# femtoBeacon_dongle_r2_0_3.net
KiCad netlist of a schematic drawn in EAGLE
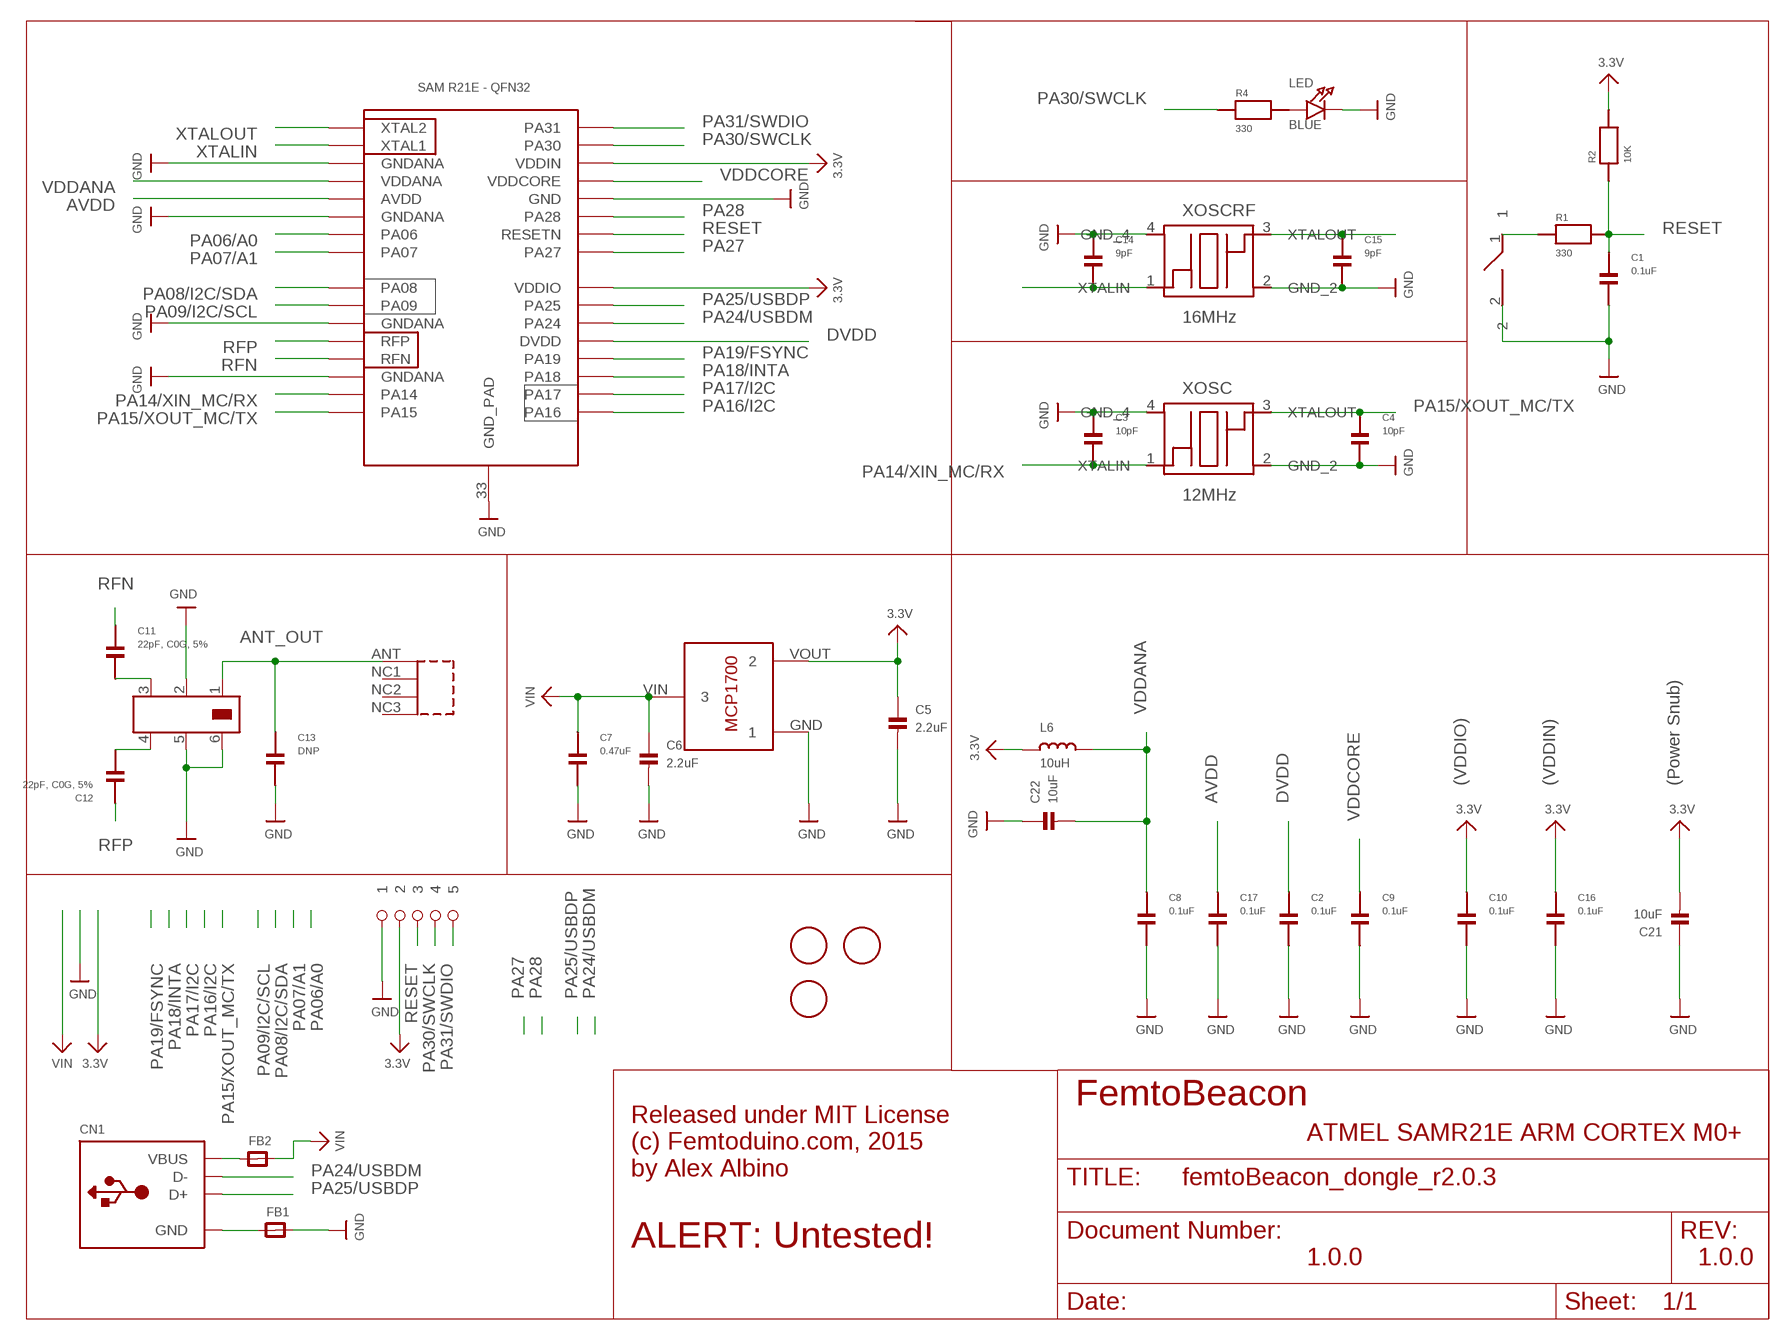
[diagram p0: schematic, sheet 1]

(export (version "E")
  (design (tool "Eeschema 10.0.6"))
  (components
    (comp (ref "BTN")
      (value "DNP")
      (footprint "eagle-import:SPST_SMD")
      (libsource (lib "eagle-import") (part "SPST_SMD"))
    )
    (comp (ref "C1")
      (value "0.1uF")
      (footprint "eagle-import:PART")
      (fields (field (name "DIGIKEY_PART") "490-3194-1-ND"))
      (libsource (lib "eagle-import") (part "CAPACITOR_0201"))
    )
    (comp (ref "C2")
      (value "0.1uF")
      (footprint "eagle-import:PART")
      (libsource (lib "eagle-import") (part "CAPACITOR_0201"))
    )
    (comp (ref "C3")
      (value "10pF")
      (footprint "eagle-import:PART")
      (fields (field (name "DIGIKEY_PART") "490-3194-1-ND"))
      (libsource (lib "eagle-import") (part "CAPACITOR_0201"))
    )
    (comp (ref "C4")
      (value "10pF")
      (footprint "eagle-import:PART")
      (fields (field (name "DIGIKEY_PART") "490-3194-1-ND"))
      (libsource (lib "eagle-import") (part "CAPACITOR_0201"))
    )
    (comp (ref "C5")
      (value "2.2uF")
      (footprint "eagle-import:_0402MP")
      (libsource (lib "eagle-import") (part "CAP_CERAMIC_0402MP"))
    )
    (comp (ref "C6")
      (value "2.2uF")
      (footprint "eagle-import:_0402MP")
      (libsource (lib "eagle-import") (part "CAP_CERAMIC_0402MP"))
    )
    (comp (ref "C7")
      (value "0.47uF")
      (footprint "eagle-import:PART")
      (libsource (lib "eagle-import") (part "CAPACITOR_0201"))
    )
    (comp (ref "C8")
      (value "0.1uF")
      (footprint "eagle-import:PART")
      (fields (field (name "DIGIKEY_PART") "490-3194-1-ND"))
      (libsource (lib "eagle-import") (part "CAPACITOR_0201"))
    )
    (comp (ref "C9")
      (value "0.1uF")
      (footprint "eagle-import:PART")
      (fields (field (name "DIGIKEY_PART") "490-3194-1-ND"))
      (libsource (lib "eagle-import") (part "CAPACITOR_0201"))
    )
    (comp (ref "C10")
      (value "0.1uF")
      (footprint "eagle-import:PART")
      (fields (field (name "DIGIKEY_PART") "490-3194-1-ND"))
      (libsource (lib "eagle-import") (part "CAPACITOR_0201"))
    )
    (comp (ref "C11")
      (value "22pF, C0G, 5%")
      (footprint "eagle-import:PART")
      (fields (field (name "DIGIKEY_PART") "490-3194-1-ND"))
      (libsource (lib "eagle-import") (part "CAPACITOR_0201"))
    )
    (comp (ref "C12")
      (value "22pF, C0G, 5%")
      (footprint "eagle-import:PART")
      (fields (field (name "DIGIKEY_PART") "490-3194-1-ND"))
      (libsource (lib "eagle-import") (part "CAPACITOR_0201"))
    )
    (comp (ref "C13")
      (value "DNP")
      (footprint "eagle-import:PART")
      (fields (field (name "DIGIKEY_PART") "490-3194-1-ND"))
      (libsource (lib "eagle-import") (part "CAPACITOR_0201"))
    )
    (comp (ref "C14")
      (value "9pF")
      (footprint "eagle-import:PART")
      (fields (field (name "DIGIKEY_PART") "490-3194-1-ND"))
      (libsource (lib "eagle-import") (part "CAPACITOR_0201"))
    )
    (comp (ref "C15")
      (value "9pF")
      (footprint "eagle-import:PART")
      (fields (field (name "DIGIKEY_PART") "490-3194-1-ND"))
      (libsource (lib "eagle-import") (part "CAPACITOR_0201"))
    )
    (comp (ref "C16")
      (value "0.1uF")
      (footprint "eagle-import:PART")
      (fields (field (name "DIGIKEY_PART") "490-3194-1-ND"))
      (libsource (lib "eagle-import") (part "CAPACITOR_0201"))
    )
    (comp (ref "C17")
      (value "0.1uF")
      (footprint "eagle-import:PART")
      (fields (field (name "DIGIKEY_PART") "490-3194-1-ND"))
      (libsource (lib "eagle-import") (part "CAPACITOR_0201"))
    )
    (comp (ref "C21")
      (value "10uF")
      (footprint "eagle-import:_0402MP")
      (libsource (lib "eagle-import") (part "CAP_CERAMIC_0402MP"))
    )
    (comp (ref "C22")
      (value "10uF")
      (footprint "eagle-import:_0402MP")
      (libsource (lib "eagle-import") (part "CAP_CERAMIC_0402MP"))
    )
    (comp (ref "CN1")
      (value "USB_TYPEA")
      (footprint "eagle-import:USB_A-SMT")
      (libsource (lib "eagle-import") (part "USB_TYPEA"))
    )
    (comp (ref "FB1")
      (value "FERRITE_0603MP")
      (footprint "eagle-import:_0603MP")
      (libsource (lib "eagle-import") (part "FERRITE_0603MP"))
    )
    (comp (ref "FB2")
      (value "FERRITE_0603MP")
      (footprint "eagle-import:_0603MP")
      (libsource (lib "eagle-import") (part "FERRITE_0603MP"))
    )
    (comp (ref "FID1")
      (value "FIDUCIAL")
      (footprint "eagle-import:FIDUCIAL_1MM")
      (libsource (lib "eagle-import") (part "FIDUCIAL"))
    )
    (comp (ref "FID2")
      (value "FIDUCIAL")
      (footprint "eagle-import:FIDUCIAL_1MM")
      (libsource (lib "eagle-import") (part "FIDUCIAL"))
    )
    (comp (ref "FID3")
      (value "FIDUCIAL")
      (footprint "eagle-import:FIDUCIAL_1MM")
      (libsource (lib "eagle-import") (part "FIDUCIAL"))
    )
    (comp (ref "L6")
      (value "10uH")
      (footprint "eagle-import:_0603MP")
      (libsource (lib "eagle-import") (part "INDUCTOR_0603MP"))
    )
    (comp (ref "LDO_VREG")
      (value "MCP1700T-3302E/TT")
      (footprint "eagle-import:MCP1700T-3302E_TT")
      (libsource (lib "eagle-import") (part "MCP1700T-3302E/TT"))
    )
    (comp (ref "LED")
      (value "BLUE")
      (footprint "eagle-import:CHIPLED_0603_NOOUTLINE")
      (libsource (lib "eagle-import") (part "LED0603_NOOUTLINE"))
    )
    (comp (ref "R1")
      (value "330")
      (footprint "eagle-import:PART")
      (libsource (lib "eagle-import") (part "RESISTOR_0201"))
    )
    (comp (ref "R2")
      (value "10K")
      (footprint "eagle-import:PART")
      (libsource (lib "eagle-import") (part "RESISTOR_0201"))
    )
    (comp (ref "R4")
      (value "330")
      (footprint "eagle-import:PART")
      (libsource (lib "eagle-import") (part "RESISTOR_0201"))
    )
    (comp (ref "U$1")
      (value "1X5_ROUND")
      (footprint "eagle-import:1X5_ROUND")
      (libsource (lib "eagle-import") (part "1X5_ROUND"))
    )
    (comp (ref "U$6")
      (value "0479480001")
      (footprint "eagle-import:0479480001")
      (libsource (lib "eagle-import") (part "0479480001"))
    )
    (comp (ref "U$12")
      (value "JOHANSON_2450BM15A0015E")
      (footprint "eagle-import:0805_BALUN")
      (libsource (lib "eagle-import") (part "JOHANSON_2450BM15A0015E"))
    )
    (comp (ref "U$76")
      (value "ATSAMR21E18A-MUT")
      (footprint "eagle-import:QFN32")
      (libsource (lib "eagle-import") (part "ATSAMR21E18A-MUT"))
    )
    (comp (ref "XOSC")
      (value "12MHz")
      (footprint "eagle-import:TSX-3225")
      (libsource (lib "eagle-import") (part "TSX-3225"))
    )
    (comp (ref "XOSCRF")
      (value "16MHz")
      (footprint "eagle-import:TSX-3225")
      (libsource (lib "eagle-import") (part "TSX-3225"))
    )
  )
  (nets
    (net (code "1") (name "/ANT_OUT") (class "Default")
      (node (ref "C13") (pin "1") (pinfunction "P$1_1") (pintype "bidirectional"))
      (node (ref "U$12") (pin "1") (pinfunction "1_1") (pintype "bidirectional"))
      (node (ref "U$6") (pin "ANT") (pinfunction "1_ANT") (pintype "bidirectional"))
    )
    (net (code "2") (name "/AVDD") (class "Default")
      (node (ref "C17") (pin "1") (pinfunction "P$1_1") (pintype "bidirectional"))
      (node (ref "U$76") (pin "5") (pinfunction "AVDD_5") (pintype "bidirectional"))
    )
    (net (code "3") (name "/DVDD") (class "Default")
      (node (ref "C2") (pin "1") (pinfunction "P$1_1") (pintype "bidirectional"))
      (node (ref "U$76") (pin "21") (pinfunction "DVDD_21") (pintype "bidirectional"))
    )
    (net (code "4") (name "/PA06{slash}A0") (class "Default")
      (node (ref "U$76") (pin "7") (pinfunction "PA06_7") (pintype "bidirectional"))
    )
    (net (code "5") (name "/PA07{slash}A1") (class "Default")
      (node (ref "U$76") (pin "8") (pinfunction "PA07_8") (pintype "bidirectional"))
    )
    (net (code "6") (name "/PA08{slash}I2C{slash}SDA") (class "Default")
      (node (ref "U$76") (pin "9") (pinfunction "PA08_9") (pintype "bidirectional"))
    )
    (net (code "7") (name "/PA09{slash}I2C{slash}SCL") (class "Default")
      (node (ref "U$76") (pin "10") (pinfunction "PA09_10") (pintype "bidirectional"))
    )
    (net (code "8") (name "/PA14{slash}XIN_MC{slash}RX") (class "Default")
      (node (ref "C3") (pin "2") (pinfunction "P$2_2") (pintype "bidirectional"))
      (node (ref "U$76") (pin "15") (pinfunction "PA14_15") (pintype "bidirectional"))
      (node (ref "XOSC") (pin "1") (pinfunction "XTALIN_1") (pintype "bidirectional"))
    )
    (net (code "9") (name "/PA15{slash}XOUT_MC{slash}TX") (class "Default")
      (node (ref "C4") (pin "1") (pinfunction "P$1_1") (pintype "bidirectional"))
      (node (ref "U$76") (pin "16") (pinfunction "PA15_16") (pintype "bidirectional"))
      (node (ref "XOSC") (pin "3") (pinfunction "XTALOUT_3") (pintype "bidirectional"))
    )
    (net (code "10") (name "/PA16{slash}I2C") (class "Default")
      (node (ref "U$76") (pin "17") (pinfunction "PA16_17") (pintype "bidirectional"))
    )
    (net (code "11") (name "/PA17{slash}I2C") (class "Default")
      (node (ref "U$76") (pin "18") (pinfunction "PA17_18") (pintype "bidirectional"))
    )
    (net (code "12") (name "/PA18{slash}INTA") (class "Default")
      (node (ref "U$76") (pin "19") (pinfunction "PA18_19") (pintype "bidirectional"))
    )
    (net (code "13") (name "/PA19{slash}FSYNC") (class "Default")
      (node (ref "U$76") (pin "20") (pinfunction "PA19_20") (pintype "bidirectional"))
    )
    (net (code "14") (name "/PA24{slash}USBDM") (class "Default")
      (node (ref "CN1") (pin "D-") (pinfunction "D-_D-") (pintype "bidirectional"))
      (node (ref "U$76") (pin "22") (pinfunction "PA24_22") (pintype "bidirectional"))
    )
    (net (code "15") (name "/PA25{slash}USBDP") (class "Default")
      (node (ref "CN1") (pin "D+") (pinfunction "D+_D+") (pintype "bidirectional"))
      (node (ref "U$76") (pin "23") (pinfunction "PA25_23") (pintype "bidirectional"))
    )
    (net (code "16") (name "/PA27") (class "Default")
      (node (ref "U$76") (pin "25") (pinfunction "PA27_25") (pintype "bidirectional"))
    )
    (net (code "17") (name "/PA28") (class "Default")
      (node (ref "U$76") (pin "27") (pinfunction "PA28_27") (pintype "bidirectional"))
    )
    (net (code "18") (name "/PA30{slash}SWCLK") (class "Default")
      (node (ref "R4") (pin "1") (pinfunction "1_1") (pintype "bidirectional"))
      (node (ref "U$1") (pin "P$4") (pinfunction "4_P$4") (pintype "bidirectional"))
      (node (ref "U$76") (pin "31") (pinfunction "PA30_31") (pintype "bidirectional"))
    )
    (net (code "19") (name "/PA31{slash}SWDIO") (class "Default")
      (node (ref "U$1") (pin "P$5") (pinfunction "5_P$5") (pintype "bidirectional"))
      (node (ref "U$76") (pin "32") (pinfunction "PA31_32") (pintype "bidirectional"))
    )
    (net (code "20") (name "/RESET") (class "Default")
      (node (ref "C1") (pin "1") (pinfunction "P$1_1") (pintype "bidirectional"))
      (node (ref "R1") (pin "2") (pinfunction "2_2") (pintype "bidirectional"))
      (node (ref "R2") (pin "1") (pinfunction "1_1") (pintype "bidirectional"))
      (node (ref "U$1") (pin "P$3") (pinfunction "3_P$3") (pintype "bidirectional"))
      (node (ref "U$76") (pin "26") (pinfunction "RESETN_26") (pintype "bidirectional"))
    )
    (net (code "21") (name "/RFN") (class "Default")
      (node (ref "C11") (pin "1") (pinfunction "P$1_1") (pintype "bidirectional"))
      (node (ref "U$76") (pin "13") (pinfunction "RFN_13") (pintype "bidirectional"))
    )
    (net (code "22") (name "/RFP") (class "Default")
      (node (ref "C12") (pin "1") (pinfunction "P$1_1") (pintype "bidirectional"))
      (node (ref "U$76") (pin "12") (pinfunction "RFP_12") (pintype "bidirectional"))
    )
    (net (code "23") (name "/VDDANA") (class "Default")
      (node (ref "C22") (pin "2") (pinfunction "P$2_2") (pintype "passive"))
      (node (ref "C8") (pin "1") (pinfunction "P$1_1") (pintype "bidirectional"))
      (node (ref "L6") (pin "2") (pinfunction "2_2") (pintype "passive"))
      (node (ref "U$76") (pin "4") (pinfunction "VDDANA_4") (pintype "bidirectional"))
    )
    (net (code "24") (name "/VDDCORE") (class "Default")
      (node (ref "C9") (pin "1") (pinfunction "P$1_1") (pintype "bidirectional"))
      (node (ref "U$76") (pin "29") (pinfunction "VDDCORE_29") (pintype "bidirectional"))
    )
    (net (code "25") (name "/XTALIN") (class "Default")
      (node (ref "C14") (pin "2") (pinfunction "P$2_2") (pintype "bidirectional"))
      (node (ref "U$76") (pin "2") (pinfunction "XTAL1_2") (pintype "bidirectional"))
      (node (ref "XOSCRF") (pin "1") (pinfunction "XTALIN_1") (pintype "bidirectional"))
    )
    (net (code "26") (name "/XTALOUT") (class "Default")
      (node (ref "C15") (pin "1") (pinfunction "P$1_1") (pintype "bidirectional"))
      (node (ref "U$76") (pin "1") (pinfunction "XTAL2_1") (pintype "bidirectional"))
      (node (ref "XOSCRF") (pin "3") (pinfunction "XTALOUT_3") (pintype "bidirectional"))
    )
    (net (code "27") (name "3.3V") (class "Default")
      (node (ref "C10") (pin "1") (pinfunction "P$1_1") (pintype "bidirectional"))
      (node (ref "C16") (pin "1") (pinfunction "P$1_1") (pintype "bidirectional"))
      (node (ref "C21") (pin "2") (pinfunction "P$2_2") (pintype "passive"))
      (node (ref "C5") (pin "1") (pinfunction "P$1_1") (pintype "passive"))
      (node (ref "L6") (pin "1") (pinfunction "1_1") (pintype "passive"))
      (node (ref "LDO_VREG") (pin "VOUT") (pinfunction "2_VOUT") (pintype "bidirectional"))
      (node (ref "R2") (pin "2") (pinfunction "2_2") (pintype "bidirectional"))
      (node (ref "U$1") (pin "P$2") (pinfunction "2_P$2") (pintype "bidirectional"))
      (node (ref "U$76") (pin "24") (pinfunction "VDDIO_24") (pintype "bidirectional"))
      (node (ref "U$76") (pin "30") (pinfunction "VDDIN_30") (pintype "bidirectional"))
    )
    (net (code "28") (name "GND") (class "Default")
      (node (ref "BTN") (pin "2") (pinfunction "2_2") (pintype "bidirectional"))
      (node (ref "C1") (pin "2") (pinfunction "P$2_2") (pintype "bidirectional"))
      (node (ref "C10") (pin "2") (pinfunction "P$2_2") (pintype "bidirectional"))
      (node (ref "C13") (pin "2") (pinfunction "P$2_2") (pintype "bidirectional"))
      (node (ref "C14") (pin "1") (pinfunction "P$1_1") (pintype "bidirectional"))
      (node (ref "C15") (pin "2") (pinfunction "P$2_2") (pintype "bidirectional"))
      (node (ref "C16") (pin "2") (pinfunction "P$2_2") (pintype "bidirectional"))
      (node (ref "C17") (pin "2") (pinfunction "P$2_2") (pintype "bidirectional"))
      (node (ref "C2") (pin "2") (pinfunction "P$2_2") (pintype "bidirectional"))
      (node (ref "C21") (pin "1") (pinfunction "P$1_1") (pintype "passive"))
      (node (ref "C22") (pin "1") (pinfunction "P$1_1") (pintype "passive"))
      (node (ref "C3") (pin "1") (pinfunction "P$1_1") (pintype "bidirectional"))
      (node (ref "C4") (pin "2") (pinfunction "P$2_2") (pintype "bidirectional"))
      (node (ref "C5") (pin "2") (pinfunction "P$2_2") (pintype "passive"))
      (node (ref "C6") (pin "2") (pinfunction "P$2_2") (pintype "passive"))
      (node (ref "C7") (pin "2") (pinfunction "P$2_2") (pintype "bidirectional"))
      (node (ref "C8") (pin "2") (pinfunction "P$2_2") (pintype "bidirectional"))
      (node (ref "C9") (pin "2") (pinfunction "P$2_2") (pintype "bidirectional"))
      (node (ref "FB1") (pin "2") (pinfunction "P$2_2") (pintype "passive"))
      (node (ref "LDO_VREG") (pin "GND") (pinfunction "1_GND") (pintype "bidirectional"))
      (node (ref "LED") (pin "C") (pinfunction "C_C") (pintype "passive"))
      (node (ref "U$1") (pin "P$1") (pinfunction "1_P$1") (pintype "bidirectional"))
      (node (ref "U$12") (pin "2") (pinfunction "2_2") (pintype "bidirectional"))
      (node (ref "U$12") (pin "5") (pinfunction "5_5") (pintype "bidirectional"))
      (node (ref "U$12") (pin "6") (pinfunction "6_6") (pintype "bidirectional"))
      (node (ref "U$76") (pin "11") (pinfunction "GNDANA_11") (pintype "bidirectional"))
      (node (ref "U$76") (pin "14") (pinfunction "GNDANA_14") (pintype "bidirectional"))
      (node (ref "U$76") (pin "28") (pinfunction "GND_28") (pintype "bidirectional"))
      (node (ref "U$76") (pin "3") (pinfunction "GNDANA_3") (pintype "bidirectional"))
      (node (ref "U$76") (pin "33") (pinfunction "GND_PAD_33") (pintype "bidirectional"))
      (node (ref "U$76") (pin "6") (pinfunction "GNDANA_6") (pintype "bidirectional"))
      (node (ref "XOSC") (pin "2") (pinfunction "GND_2_2") (pintype "bidirectional"))
      (node (ref "XOSC") (pin "4") (pinfunction "GND_4_4") (pintype "bidirectional"))
      (node (ref "XOSCRF") (pin "2") (pinfunction "GND_2_2") (pintype "bidirectional"))
      (node (ref "XOSCRF") (pin "4") (pinfunction "GND_4_4") (pintype "bidirectional"))
    )
    (net (code "29") (name "Net-(BTN-Pad1)") (class "Default")
      (node (ref "BTN") (pin "1") (pinfunction "1_1") (pintype "bidirectional"))
      (node (ref "R1") (pin "1") (pinfunction "1_1") (pintype "bidirectional"))
    )
    (net (code "30") (name "Net-(C11-P$2)") (class "Default")
      (node (ref "C11") (pin "2") (pinfunction "P$2_2") (pintype "bidirectional"))
      (node (ref "U$12") (pin "3") (pinfunction "3_3") (pintype "bidirectional"))
    )
    (net (code "31") (name "Net-(C12-P$2)") (class "Default")
      (node (ref "C12") (pin "2") (pinfunction "P$2_2") (pintype "bidirectional"))
      (node (ref "U$12") (pin "4") (pinfunction "4_4") (pintype "bidirectional"))
    )
    (net (code "32") (name "Net-(FB1-P$1)") (class "Default")
      (node (ref "CN1") (pin "GND") (pinfunction "GND_GND") (pintype "power_in"))
      (node (ref "FB1") (pin "1") (pinfunction "P$1_1") (pintype "passive"))
    )
    (net (code "33") (name "Net-(FB2-P$1)") (class "Default")
      (node (ref "CN1") (pin "VBUS") (pinfunction "VBUS_VBUS") (pintype "power_in"))
      (node (ref "FB2") (pin "1") (pinfunction "P$1_1") (pintype "passive"))
    )
    (net (code "34") (name "Net-(LED-PadA)") (class "Default")
      (node (ref "LED") (pin "A") (pinfunction "A_A") (pintype "passive"))
      (node (ref "R4") (pin "2") (pinfunction "2_2") (pintype "bidirectional"))
    )
    (net (code "35") (name "VIN") (class "Default")
      (node (ref "C6") (pin "1") (pinfunction "P$1_1") (pintype "passive"))
      (node (ref "C7") (pin "1") (pinfunction "P$1_1") (pintype "bidirectional"))
      (node (ref "FB2") (pin "2") (pinfunction "P$2_2") (pintype "passive"))
      (node (ref "LDO_VREG") (pin "VIN") (pinfunction "3_VIN") (pintype "bidirectional"))
    )
    (net (code "36") (name "unconnected-(U$6-2-PadNC1)") (class "Default")
      (node (ref "U$6") (pin "NC1") (pinfunction "2_NC1") (pintype "bidirectional"))
    )
    (net (code "37") (name "unconnected-(U$6-3-PadNC2)") (class "Default")
      (node (ref "U$6") (pin "NC2") (pinfunction "3_NC2") (pintype "bidirectional"))
    )
    (net (code "38") (name "unconnected-(U$6-4-PadNC3)") (class "Default")
      (node (ref "U$6") (pin "NC3") (pinfunction "4_NC3") (pintype "bidirectional"))
    )
  )
)
